# microcontroller.net
KiCad netlist of a schematic drawn in Altium Designer
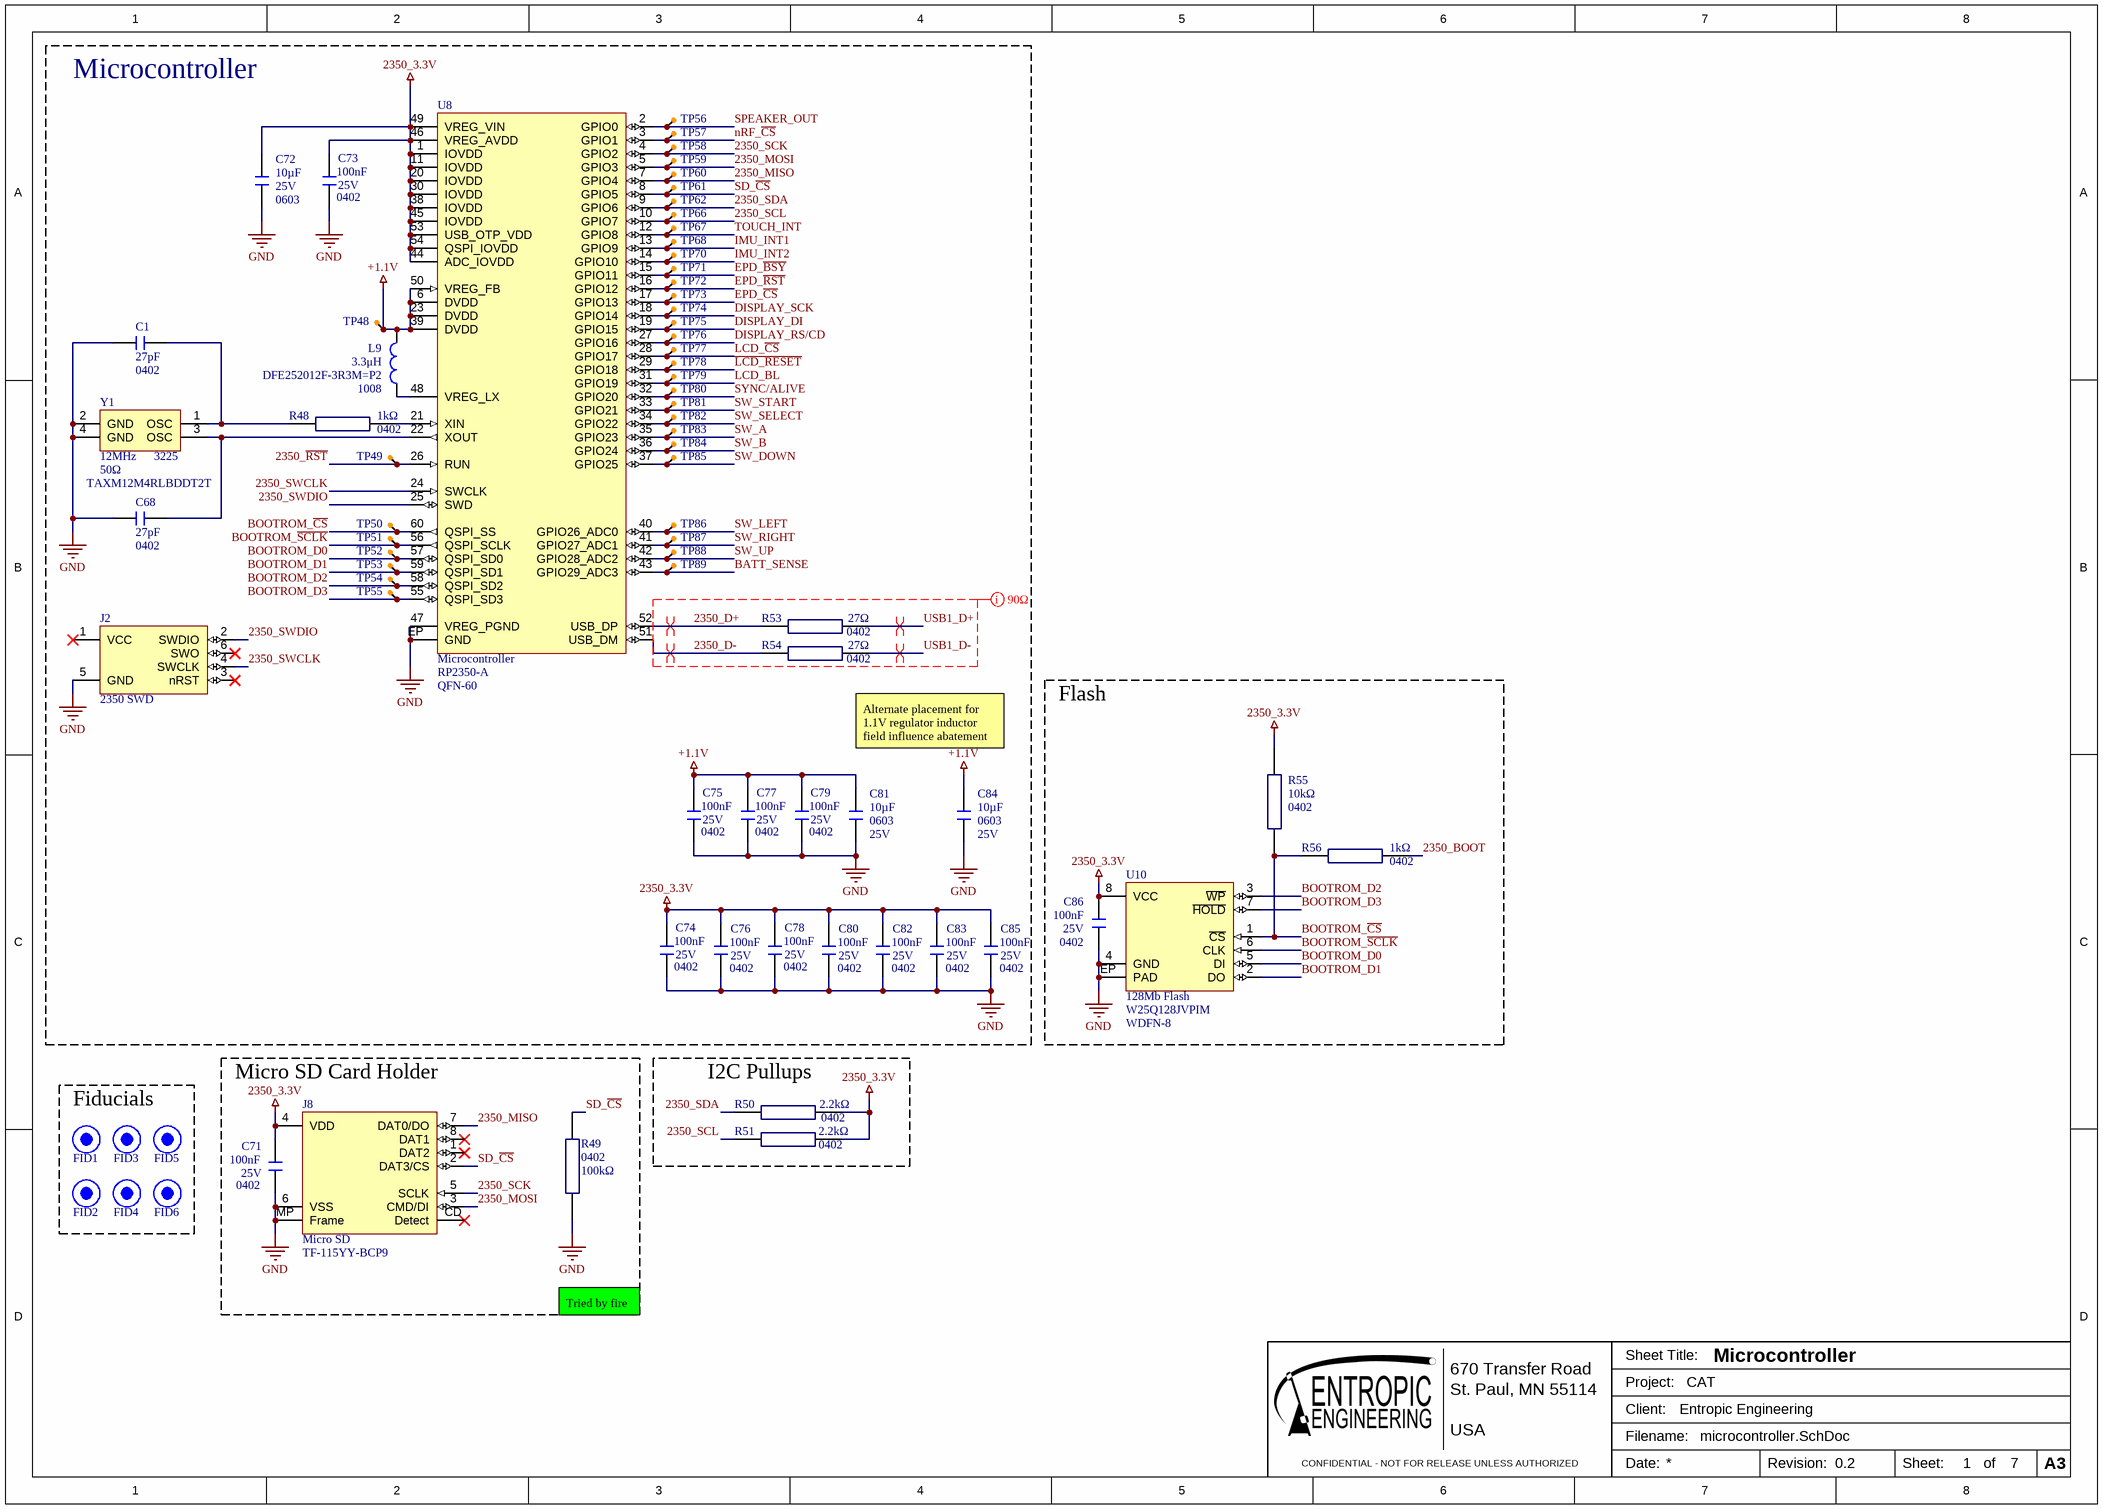
[diagram p0: microcontroller.SchDoc]

(export (version "E")
  (design (tool "Eeschema 10.0.6"))
  (components
    (comp (ref "C1")
      (value "27pF")
      (footprint "0402_capacitor")
      (description "27 pF, 25 V, X7R, 0402 Chip capacitor")
      (fields
        (field (name "MANUFACTURER") "Yageo")
        (field (name "MANUFACTURER PART NUMBER") "CC0402JRNPO9BN270")
        (field (name "CASE/PACKAGE") "0402")
      )
      (libsource (lib "cat") (part "CC0402JRNPO9BN270"))
    )
    (comp (ref "C68")
      (value "27pF")
      (footprint "0402_capacitor")
      (description "27 pF, 25 V, X7R, 0402 Chip capacitor")
      (fields
        (field (name "MANUFACTURER") "Yageo")
        (field (name "MANUFACTURER PART NUMBER") "CC0402JRNPO9BN270")
        (field (name "CASE/PACKAGE") "0402")
      )
      (libsource (lib "cat") (part "CC0402JRNPO9BN270"))
    )
    (comp (ref "C71")
      (value "GRM155R71E104KE14D")
      (footprint "0402_capacitor")
      (description "100 nF, 25 V, X7R, 0402 Chip capacitor")
      (fields
        (field (name "MANUFACTURER") "Murata")
        (field (name "TOLERANCE") "10%")
        (field (name "CASE CODE (IMPERIAL)") "0402")
        (field (name "VOLTAGE") "25V")
        (field (name "CAPACITANCE") "100nF")
      )
      (libsource (lib "cat") (part "GRM155R71E104KE14D"))
    )
    (comp (ref "C72")
      (value "10µF")
      (footprint "0603_capacitor")
      (description "10 µF, 25 V, X5R, 0603 Chip capacitor")
      (fields
        (field (name "MANUFACTURER") "Samsung")
        (field (name "TOLERANCE") "20%")
        (field (name "VOLTAGE RATING") "25V")
        (field (name "CASE/PACKAGE") "0603")
      )
      (libsource (lib "cat") (part "CL10A106MA8NRNC"))
    )
    (comp (ref "C73")
      (value "GRM155R71E104KE14D")
      (footprint "0402_capacitor")
      (description "100 nF, 25 V, X7R, 0402 Chip capacitor")
      (fields
        (field (name "MANUFACTURER") "Murata")
        (field (name "TOLERANCE") "10%")
        (field (name "CASE CODE (IMPERIAL)") "0402")
        (field (name "VOLTAGE") "25V")
        (field (name "CAPACITANCE") "100nF")
      )
      (libsource (lib "cat") (part "GRM155R71E104KE14D"))
    )
    (comp (ref "C74")
      (value "GRM155R71E104KE14D")
      (footprint "0402_capacitor")
      (description "100 nF, 25 V, X7R, 0402 Chip capacitor")
      (fields
        (field (name "MANUFACTURER") "Murata")
        (field (name "TOLERANCE") "10%")
        (field (name "CASE CODE (IMPERIAL)") "0402")
        (field (name "VOLTAGE") "25V")
        (field (name "CAPACITANCE") "100nF")
      )
      (libsource (lib "cat") (part "GRM155R71E104KE14D"))
    )
    (comp (ref "C75")
      (value "GRM155R71E104KE14D")
      (footprint "0402_capacitor")
      (description "100 nF, 25 V, X7R, 0402 Chip capacitor")
      (fields
        (field (name "MANUFACTURER") "Murata")
        (field (name "TOLERANCE") "10%")
        (field (name "CASE CODE (IMPERIAL)") "0402")
        (field (name "VOLTAGE") "25V")
        (field (name "CAPACITANCE") "100nF")
      )
      (libsource (lib "cat") (part "GRM155R71E104KE14D"))
    )
    (comp (ref "C76")
      (value "GRM155R71E104KE14D")
      (footprint "0402_capacitor")
      (description "100 nF, 25 V, X7R, 0402 Chip capacitor")
      (fields
        (field (name "MANUFACTURER") "Murata")
        (field (name "TOLERANCE") "10%")
        (field (name "CASE CODE (IMPERIAL)") "0402")
        (field (name "VOLTAGE") "25V")
        (field (name "CAPACITANCE") "100nF")
      )
      (libsource (lib "cat") (part "GRM155R71E104KE14D"))
    )
    (comp (ref "C77")
      (value "GRM155R71E104KE14D")
      (footprint "0402_capacitor")
      (description "100 nF, 25 V, X7R, 0402 Chip capacitor")
      (fields
        (field (name "MANUFACTURER") "Murata")
        (field (name "TOLERANCE") "10%")
        (field (name "CASE CODE (IMPERIAL)") "0402")
        (field (name "VOLTAGE") "25V")
        (field (name "CAPACITANCE") "100nF")
      )
      (libsource (lib "cat") (part "GRM155R71E104KE14D"))
    )
    (comp (ref "C78")
      (value "GRM155R71E104KE14D")
      (footprint "0402_capacitor")
      (description "100 nF, 25 V, X7R, 0402 Chip capacitor")
      (fields
        (field (name "MANUFACTURER") "Murata")
        (field (name "TOLERANCE") "10%")
        (field (name "CASE CODE (IMPERIAL)") "0402")
        (field (name "VOLTAGE") "25V")
        (field (name "CAPACITANCE") "100nF")
      )
      (libsource (lib "cat") (part "GRM155R71E104KE14D"))
    )
    (comp (ref "C79")
      (value "GRM155R71E104KE14D")
      (footprint "0402_capacitor")
      (description "100 nF, 25 V, X7R, 0402 Chip capacitor")
      (fields
        (field (name "MANUFACTURER") "Murata")
        (field (name "TOLERANCE") "10%")
        (field (name "CASE CODE (IMPERIAL)") "0402")
        (field (name "VOLTAGE") "25V")
        (field (name "CAPACITANCE") "100nF")
      )
      (libsource (lib "cat") (part "GRM155R71E104KE14D"))
    )
    (comp (ref "C80")
      (value "GRM155R71E104KE14D")
      (footprint "0402_capacitor")
      (description "100 nF, 25 V, X7R, 0402 Chip capacitor")
      (fields
        (field (name "MANUFACTURER") "Murata")
        (field (name "TOLERANCE") "10%")
        (field (name "CASE CODE (IMPERIAL)") "0402")
        (field (name "VOLTAGE") "25V")
        (field (name "CAPACITANCE") "100nF")
      )
      (libsource (lib "cat") (part "GRM155R71E104KE14D"))
    )
    (comp (ref "C81")
      (value "10µF")
      (footprint "0603_capacitor")
      (description "10 µF, 25 V, X5R, 0603 Chip capacitor")
      (fields
        (field (name "MANUFACTURER") "Samsung")
        (field (name "TOLERANCE") "20%")
        (field (name "VOLTAGE RATING") "25V")
        (field (name "CASE/PACKAGE") "0603")
      )
      (libsource (lib "cat") (part "CL10A106MA8NRNC"))
    )
    (comp (ref "C82")
      (value "GRM155R71E104KE14D")
      (footprint "0402_capacitor")
      (description "100 nF, 25 V, X7R, 0402 Chip capacitor")
      (fields
        (field (name "MANUFACTURER") "Murata")
        (field (name "TOLERANCE") "10%")
        (field (name "CASE CODE (IMPERIAL)") "0402")
        (field (name "VOLTAGE") "25V")
        (field (name "CAPACITANCE") "100nF")
      )
      (libsource (lib "cat") (part "GRM155R71E104KE14D"))
    )
    (comp (ref "C83")
      (value "GRM155R71E104KE14D")
      (footprint "0402_capacitor")
      (description "100 nF, 25 V, X7R, 0402 Chip capacitor")
      (fields
        (field (name "MANUFACTURER") "Murata")
        (field (name "TOLERANCE") "10%")
        (field (name "CASE CODE (IMPERIAL)") "0402")
        (field (name "VOLTAGE") "25V")
        (field (name "CAPACITANCE") "100nF")
      )
      (libsource (lib "cat") (part "GRM155R71E104KE14D"))
    )
    (comp (ref "C84")
      (value "10µF")
      (footprint "0603_capacitor")
      (description "10 µF, 25 V, X5R, 0603 Chip capacitor")
      (fields
        (field (name "MANUFACTURER") "Samsung")
        (field (name "TOLERANCE") "20%")
        (field (name "VOLTAGE RATING") "25V")
        (field (name "CASE/PACKAGE") "0603")
      )
      (libsource (lib "cat") (part "CL10A106MA8NRNC"))
    )
    (comp (ref "C85")
      (value "GRM155R71E104KE14D")
      (footprint "0402_capacitor")
      (description "100 nF, 25 V, X7R, 0402 Chip capacitor")
      (fields
        (field (name "MANUFACTURER") "Murata")
        (field (name "TOLERANCE") "10%")
        (field (name "CASE CODE (IMPERIAL)") "0402")
        (field (name "VOLTAGE") "25V")
        (field (name "CAPACITANCE") "100nF")
      )
      (libsource (lib "cat") (part "GRM155R71E104KE14D"))
    )
    (comp (ref "C86")
      (value "GRM155R71E104KE14D")
      (footprint "0402_capacitor")
      (description "100 nF, 25 V, X7R, 0402 Chip capacitor")
      (fields
        (field (name "MANUFACTURER") "Murata")
        (field (name "TOLERANCE") "10%")
        (field (name "CASE CODE (IMPERIAL)") "0402")
        (field (name "VOLTAGE") "25V")
        (field (name "CAPACITANCE") "100nF")
      )
      (libsource (lib "cat") (part "GRM155R71E104KE14D"))
    )
    (comp (ref "FID1")
      (value "fiducial")
      (footprint "fiducial-0.5")
      (description "0.5mm diameter round fiducial")
      (fields (field (name "HOUSE_PART_NUMBER") "Disc-0.5"))
      (libsource (lib "cat") (part "fiducial"))
    )
    (comp (ref "FID2")
      (value "fiducial")
      (footprint "fiducial-0.5")
      (description "0.5mm diameter round fiducial")
      (fields (field (name "HOUSE_PART_NUMBER") "Disc-0.5"))
      (libsource (lib "cat") (part "fiducial"))
    )
    (comp (ref "FID3")
      (value "fiducial")
      (footprint "fiducial-0.5")
      (description "0.5mm diameter round fiducial")
      (fields (field (name "HOUSE_PART_NUMBER") "Disc-0.5"))
      (libsource (lib "cat") (part "fiducial"))
    )
    (comp (ref "FID4")
      (value "fiducial")
      (footprint "fiducial-0.5")
      (description "0.5mm diameter round fiducial")
      (fields (field (name "HOUSE_PART_NUMBER") "Disc-0.5"))
      (libsource (lib "cat") (part "fiducial"))
    )
    (comp (ref "FID5")
      (value "fiducial")
      (footprint "fiducial-0.5")
      (description "0.5mm diameter round fiducial")
      (fields (field (name "HOUSE_PART_NUMBER") "Disc-0.5"))
      (libsource (lib "cat") (part "fiducial"))
    )
    (comp (ref "FID6")
      (value "fiducial")
      (footprint "fiducial-0.5")
      (description "0.5mm diameter round fiducial")
      (fields (field (name "HOUSE_PART_NUMBER") "Disc-0.5"))
      (libsource (lib "cat") (part "fiducial"))
    )
    (comp (ref "J2")
      (value "2350 SWD")
      (footprint "debug_header_dual")
      (description "Mates with TC-2030-CTX-NL")
      (fields (field (name "HOUSE_PART_NUMBER") "type-value-case-grade"))
      (libsource (lib "cat") (part "TAG_CONN_CTX"))
    )
    (comp (ref "J8")
      (value "Micro SD")
      (footprint "TF-115YY-BCP9")
      (description "Micro SD card holder")
      (fields
        (field (name "MANUFACTURER") "Xunpu")
        (field (name "MANUFACTURER PART NUMBER") "TF-115YY-BCP9")
        (field (name "HOUSE_PART_NUMBER") "TF-115YY-BCP9")
      )
      (libsource (lib "cat") (part "TF-115YY-BCP9"))
    )
    (comp (ref "L9")
      (value "3.3μH")
      (footprint "INDC2520X12N")
      (description "3.3 μH, 1.8 A, 1008 Inductor")
      (fields
        (field (name "MANUFACTURER") "Murata")
        (field (name "TOLERANCE") "20%")
        (field (name "CASE CODE (IMPERIAL)") "1008")
        (field (name "MANUFACTURER PART NUMBER") "DFE252012F-3R3M=P2")
      )
      (libsource (lib "cat") (part "DFE252012F-3R3M=P2"))
    )
    (comp (ref "R48")
      (value "1kΩ")
      (footprint "0402_resistor")
      (description "1 kΩ, 0402 Chip resistor")
      (fields
        (field (name "MANUFACTURER") "Yageo")
        (field (name "MANUFACTURER PART NUMBER") "RC0402JR-071KL")
        (field (name "CASE/PACKAGE") "0402")
      )
      (libsource (lib "cat") (part "RC0402JR-071KL"))
    )
    (comp (ref "R49")
      (value "100kΩ")
      (footprint "0402_resistor")
      (description "100 kΩ, 0402 Chip resistor")
      (fields
        (field (name "MANUFACTURER") "Yageo")
        (field (name "MANUFACTURER PART NUMBER") "RC0402FR-07100KL")
        (field (name "CASE/PACKAGE") "0402")
      )
      (libsource (lib "cat") (part "RC0402FR-07100KL"))
    )
    (comp (ref "R50")
      (value "2.2kΩ")
      (footprint "0402_resistor")
      (description "2.2 kΩ, 0402 Chip resistor")
      (fields
        (field (name "MANUFACTURER") "Yageo")
        (field (name "MANUFACTURER PART NUMBER") "RC0402FR-072K2L")
        (field (name "CASE/PACKAGE") "0402")
      )
      (libsource (lib "cat") (part "RC0402FR-072K2L"))
    )
    (comp (ref "R51")
      (value "2.2kΩ")
      (footprint "0402_resistor")
      (description "2.2 kΩ, 0402 Chip resistor")
      (fields
        (field (name "MANUFACTURER") "Yageo")
        (field (name "MANUFACTURER PART NUMBER") "RC0402FR-072K2L")
        (field (name "CASE/PACKAGE") "0402")
      )
      (libsource (lib "cat") (part "RC0402FR-072K2L"))
    )
    (comp (ref "R53")
      (value "RMCF0402FT27R0")
      (footprint "0402_resistor")
      (description "27 Ω, 0402 Chip resistor")
      (fields
        (field (name "MANUFACTURER") "Stackpole Electronics")
        (field (name "TOLERANCE") "1%")
        (field (name "RESISTANCE") "27Ω")
        (field (name "SIZE CODE") "0402")
      )
      (libsource (lib "cat") (part "RMCF0402FT27R0"))
    )
    (comp (ref "R54")
      (value "RMCF0402FT27R0")
      (footprint "0402_resistor")
      (description "27 Ω, 0402 Chip resistor")
      (fields
        (field (name "MANUFACTURER") "Stackpole Electronics")
        (field (name "TOLERANCE") "1%")
        (field (name "RESISTANCE") "27Ω")
        (field (name "SIZE CODE") "0402")
      )
      (libsource (lib "cat") (part "RMCF0402FT27R0"))
    )
    (comp (ref "R55")
      (value "RMCF0402FT10K0")
      (footprint "0402_resistor")
      (description "10 kΩ, 0402 Chip resistor")
      (fields
        (field (name "MANUFACTURER") "Stackpole Electronics")
        (field (name "TOLERANCE") "1%")
        (field (name "CASE CODE (IMPERIAL)") "0402")
        (field (name "RESISTANCE") "10kΩ")
      )
      (libsource (lib "cpc") (part "RMCF0402FT10K0"))
    )
    (comp (ref "R56")
      (value "1kΩ")
      (footprint "0402_resistor")
      (description "1 kΩ, 0402 Chip resistor")
      (fields
        (field (name "MANUFACTURER") "Yageo")
        (field (name "MANUFACTURER PART NUMBER") "RC0402JR-071KL")
        (field (name "CASE/PACKAGE") "0402")
      )
      (libsource (lib "cpc") (part "RC0402JR-071KL"))
    )
    (comp (ref "TP48")
      (value "+1.1V")
      (footprint "test_point-1")
      (description "Test point")
      (libsource (lib "cat") (part "test_point-1"))
    )
    (comp (ref "TP49")
      (value "test_point-1")
      (footprint "test_point-1")
      (description "Test point")
      (libsource (lib "cat") (part "test_point-1"))
    )
    (comp (ref "TP50")
      (value "test_point-1")
      (footprint "test_point-1")
      (description "Test point")
      (libsource (lib "cat") (part "test_point-1"))
    )
    (comp (ref "TP51")
      (value "test_point-1")
      (footprint "test_point-1")
      (description "Test point")
      (libsource (lib "cat") (part "test_point-1"))
    )
    (comp (ref "TP52")
      (value "test_point-1")
      (footprint "test_point-1")
      (description "Test point")
      (libsource (lib "cat") (part "test_point-1"))
    )
    (comp (ref "TP53")
      (value "test_point-1")
      (footprint "test_point-1")
      (description "Test point")
      (libsource (lib "cat") (part "test_point-1"))
    )
    (comp (ref "TP54")
      (value "test_point-1")
      (footprint "test_point-1")
      (description "Test point")
      (libsource (lib "cat") (part "test_point-1"))
    )
    (comp (ref "TP55")
      (value "test_point-1")
      (footprint "test_point-1")
      (description "Test point")
      (libsource (lib "cat") (part "test_point-1"))
    )
    (comp (ref "TP56")
      (value "test_point-1")
      (footprint "test_point-1")
      (description "Test point")
      (libsource (lib "cat") (part "test_point-1"))
    )
    (comp (ref "TP57")
      (value "test_point-1")
      (footprint "test_point-1")
      (description "Test point")
      (libsource (lib "cat") (part "test_point-1"))
    )
    (comp (ref "TP58")
      (value "test_point-1")
      (footprint "test_point-1")
      (description "Test point")
      (libsource (lib "cat") (part "test_point-1"))
    )
    (comp (ref "TP59")
      (value "test_point-1")
      (footprint "test_point-1")
      (description "Test point")
      (libsource (lib "cat") (part "test_point-1"))
    )
    (comp (ref "TP60")
      (value "test_point-1")
      (footprint "test_point-1")
      (description "Test point")
      (libsource (lib "cat") (part "test_point-1"))
    )
    (comp (ref "TP61")
      (value "test_point-1")
      (footprint "test_point-1")
      (description "Test point")
      (libsource (lib "cat") (part "test_point-1"))
    )
    (comp (ref "TP62")
      (value "test_point-1")
      (footprint "test_point-1")
      (description "Test point")
      (libsource (lib "cat") (part "test_point-1"))
    )
    (comp (ref "TP66")
      (value "test_point-1")
      (footprint "test_point-1")
      (description "Test point")
      (libsource (lib "cat") (part "test_point-1"))
    )
    (comp (ref "TP67")
      (value "test_point-1")
      (footprint "test_point-1")
      (description "Test point")
      (libsource (lib "cat") (part "test_point-1"))
    )
    (comp (ref "TP68")
      (value "test_point-1")
      (footprint "test_point-1")
      (description "Test point")
      (libsource (lib "cat") (part "test_point-1"))
    )
    (comp (ref "TP70")
      (value "test_point-1")
      (footprint "test_point-1")
      (description "Test point")
      (libsource (lib "cat") (part "test_point-1"))
    )
    (comp (ref "TP71")
      (value "test_point-1")
      (footprint "test_point-1")
      (description "Test point")
      (libsource (lib "cat") (part "test_point-1"))
    )
    (comp (ref "TP72")
      (value "test_point-1")
      (footprint "test_point-1")
      (description "Test point")
      (libsource (lib "cat") (part "test_point-1"))
    )
    (comp (ref "TP73")
      (value "test_point-1")
      (footprint "test_point-1")
      (description "Test point")
      (libsource (lib "cat") (part "test_point-1"))
    )
    (comp (ref "TP74")
      (value "test_point-1")
      (footprint "test_point-1")
      (description "Test point")
      (libsource (lib "cat") (part "test_point-1"))
    )
    (comp (ref "TP75")
      (value "test_point-1")
      (footprint "test_point-1")
      (description "Test point")
      (libsource (lib "cat") (part "test_point-1"))
    )
    (comp (ref "TP76")
      (value "test_point-1")
      (footprint "test_point-1")
      (description "Test point")
      (libsource (lib "cat") (part "test_point-1"))
    )
    (comp (ref "TP77")
      (value "test_point-1")
      (footprint "test_point-1")
      (description "Test point")
      (libsource (lib "cat") (part "test_point-1"))
    )
    (comp (ref "TP78")
      (value "test_point-1")
      (footprint "test_point-1")
      (description "Test point")
      (libsource (lib "cat") (part "test_point-1"))
    )
    (comp (ref "TP79")
      (value "test_point-1")
      (footprint "test_point-1")
      (description "Test point")
      (libsource (lib "cat") (part "test_point-1"))
    )
    (comp (ref "TP80")
      (value "test_point-1")
      (footprint "test_point-1")
      (description "Test point")
      (libsource (lib "cat") (part "test_point-1"))
    )
    (comp (ref "TP81")
      (value "test_point-1")
      (footprint "test_point-1")
      (description "Test point")
      (libsource (lib "cat") (part "test_point-1"))
    )
    (comp (ref "TP82")
      (value "test_point-1")
      (footprint "test_point-1")
      (description "Test point")
      (libsource (lib "cat") (part "test_point-1"))
    )
    (comp (ref "TP83")
      (value "test_point-1")
      (footprint "test_point-1")
      (description "Test point")
      (libsource (lib "cat") (part "test_point-1"))
    )
    (comp (ref "TP84")
      (value "test_point-1")
      (footprint "test_point-1")
      (description "Test point")
      (libsource (lib "cat") (part "test_point-1"))
    )
    (comp (ref "TP85")
      (value "test_point-1")
      (footprint "test_point-1")
      (description "Test point")
      (libsource (lib "cat") (part "test_point-1"))
    )
    (comp (ref "TP86")
      (value "test_point-1")
      (footprint "test_point-1")
      (description "Test point")
      (libsource (lib "cat") (part "test_point-1"))
    )
    (comp (ref "TP87")
      (value "test_point-1")
      (footprint "test_point-1")
      (description "Test point")
      (libsource (lib "cat") (part "test_point-1"))
    )
    (comp (ref "TP88")
      (value "test_point-1")
      (footprint "test_point-1")
      (description "Test point")
      (libsource (lib "cat") (part "test_point-1"))
    )
    (comp (ref "TP89")
      (value "test_point-1")
      (footprint "test_point-1")
      (description "Test point")
      (libsource (lib "cat") (part "test_point-1"))
    )
    (comp (ref "U8")
      (value "Microcontroller")
      (footprint "PQFN40P700X700X80_HS-61N")
      (description "Microcontroller, QFN-60")
      (fields
        (field (name "MANUFACTURER") "Raspberry Pi")
        (field (name "PACKAGE") "QFN-60")
        (field (name "MANUFACTURER PART NUMBER") "RP2350-A")
        (field (name "HOUSE_PART_NUMBER") "RP2350-A")
      )
      (libsource (lib "cat") (part "RP2350-A"))
    )
    (comp (ref "U10")
      (value "128Mb Flash")
      (footprint "WDFN-8")
      (description "128Mb SPI flash memory")
      (fields
        (field (name "MANUFACTURER") "Winbond")
        (field (name "CASE/PACKAGE") "WDFN-8")
        (field (name "MANUFACTURER PART NUMBER") "W25Q128JVPIM")
      )
      (libsource (lib "cat") (part "W25Q128JVPIM"))
    )
    (comp (ref "Y1")
      (value "12MHz")
      (footprint "3225_crystal")
      (description "12 MHz, 10 ppm, 20 pF, 3225 Crystal")
      (fields
        (field (name "MANUFACTURER PART NUMBER") "TAXM12M4RLBDDT2T")
        (field (name "CASE/PACKAGE") "3225")
        (field (name "ESR") "50Ω")
        (field (name "HOUSE_PART_NUMBER") "TAXM12M4RLBDDT2T")
      )
      (libsource (lib "cat") (part "TAXM12M4RLBDDT2T"))
    )
  )
  (nets
    (net (code "1") (name "+1.1V") (class "Default")
      (node (ref "C75") (pin "2") (pinfunction "2_2") (pintype "passive"))
      (node (ref "C77") (pin "2") (pinfunction "2_2") (pintype "passive"))
      (node (ref "C79") (pin "2") (pinfunction "2_2") (pintype "passive"))
      (node (ref "C81") (pin "2") (pinfunction "2_2") (pintype "passive"))
      (node (ref "C84") (pin "2") (pinfunction "2_2") (pintype "passive"))
      (node (ref "L9") (pin "2") (pinfunction "2_2") (pintype "passive"))
      (node (ref "TP48") (pin "1") (pinfunction "1_1") (pintype "passive"))
      (node (ref "U8") (pin "23") (pinfunction "DVDD_23") (pintype "power_in"))
      (node (ref "U8") (pin "39") (pinfunction "DVDD_39") (pintype "power_in"))
      (node (ref "U8") (pin "50") (pinfunction "VREG_FB_50") (pintype "input"))
      (node (ref "U8") (pin "6") (pinfunction "DVDD_6") (pintype "power_in"))
    )
    (net (code "2") (name "/2350_BOOT") (class "Default")
      (node (ref "R56") (pin "2") (pinfunction "2_2") (pintype "passive"))
    )
    (net (code "3") (name "/2350_D+") (class "Default")
      (node (ref "R53") (pin "1") (pinfunction "1_1") (pintype "passive"))
      (node (ref "U8") (pin "52") (pinfunction "USB_DP_52") (pintype "bidirectional"))
    )
    (net (code "4") (name "/2350_D-") (class "Default")
      (node (ref "R54") (pin "1") (pinfunction "1_1") (pintype "passive"))
      (node (ref "U8") (pin "51") (pinfunction "USB_DM_51") (pintype "bidirectional"))
    )
    (net (code "5") (name "/2350_MISO") (class "Default")
      (node (ref "J8") (pin "7") (pinfunction "DAT0/DO_7") (pintype "bidirectional"))
      (node (ref "TP60") (pin "1") (pinfunction "1_1") (pintype "passive"))
      (node (ref "U8") (pin "7") (pinfunction "GPIO4_7") (pintype "bidirectional"))
    )
    (net (code "6") (name "/2350_MOSI") (class "Default")
      (node (ref "J8") (pin "3") (pinfunction "CMD/DI_3") (pintype "bidirectional"))
      (node (ref "TP59") (pin "1") (pinfunction "1_1") (pintype "passive"))
      (node (ref "U8") (pin "5") (pinfunction "GPIO3_5") (pintype "bidirectional"))
    )
    (net (code "7") (name "/2350_SCK") (class "Default")
      (node (ref "J8") (pin "5") (pinfunction "SCLK_5") (pintype "input"))
      (node (ref "TP58") (pin "1") (pinfunction "1_1") (pintype "passive"))
      (node (ref "U8") (pin "4") (pinfunction "GPIO2_4") (pintype "bidirectional"))
    )
    (net (code "8") (name "/2350_SCL") (class "Default")
      (node (ref "R51") (pin "2") (pinfunction "2_2") (pintype "passive"))
      (node (ref "TP66") (pin "1") (pinfunction "1_1") (pintype "passive"))
      (node (ref "U8") (pin "10") (pinfunction "GPIO7_10") (pintype "bidirectional"))
    )
    (net (code "9") (name "/2350_SDA") (class "Default")
      (node (ref "R50") (pin "2") (pinfunction "2_2") (pintype "passive"))
      (node (ref "TP62") (pin "1") (pinfunction "1_1") (pintype "passive"))
      (node (ref "U8") (pin "9") (pinfunction "GPIO6_9") (pintype "bidirectional"))
    )
    (net (code "10") (name "/2350_SWCLK") (class "Default")
      (node (ref "J2") (pin "4") (pinfunction "SWCLK_4") (pintype "bidirectional"))
      (node (ref "U8") (pin "24") (pinfunction "SWCLK_24") (pintype "input"))
    )
    (net (code "11") (name "/2350_SWDIO") (class "Default")
      (node (ref "J2") (pin "2") (pinfunction "SWDIO_2") (pintype "bidirectional"))
      (node (ref "U8") (pin "25") (pinfunction "SWD_25") (pintype "bidirectional"))
    )
    (net (code "12") (name "/2350_~{RST}") (class "Default")
      (node (ref "TP49") (pin "1") (pinfunction "1_1") (pintype "passive"))
      (node (ref "U8") (pin "26") (pinfunction "RUN_26") (pintype "input"))
    )
    (net (code "13") (name "/BATT_SENSE") (class "Default")
      (node (ref "TP89") (pin "1") (pinfunction "1_1") (pintype "passive"))
      (node (ref "U8") (pin "43") (pinfunction "GPIO29_ADC3_43") (pintype "bidirectional"))
    )
    (net (code "14") (name "/BOOTROM_D0") (class "Default")
      (node (ref "TP52") (pin "1") (pinfunction "1_1") (pintype "passive"))
      (node (ref "U10") (pin "5") (pinfunction "DI_5") (pintype "bidirectional"))
      (node (ref "U8") (pin "57") (pinfunction "QSPI_SD0_57") (pintype "bidirectional"))
    )
    (net (code "15") (name "/BOOTROM_D1") (class "Default")
      (node (ref "TP53") (pin "1") (pinfunction "1_1") (pintype "passive"))
      (node (ref "U10") (pin "2") (pinfunction "DO_2") (pintype "bidirectional"))
      (node (ref "U8") (pin "59") (pinfunction "QSPI_SD1_59") (pintype "bidirectional"))
    )
    (net (code "16") (name "/BOOTROM_D2") (class "Default")
      (node (ref "TP54") (pin "1") (pinfunction "1_1") (pintype "passive"))
      (node (ref "U10") (pin "3") (pinfunction "~{WP}_3") (pintype "bidirectional"))
      (node (ref "U8") (pin "58") (pinfunction "QSPI_SD2_58") (pintype "bidirectional"))
    )
    (net (code "17") (name "/BOOTROM_D3") (class "Default")
      (node (ref "TP55") (pin "1") (pinfunction "1_1") (pintype "passive"))
      (node (ref "U10") (pin "7") (pinfunction "~{HOLD}_7") (pintype "bidirectional"))
      (node (ref "U8") (pin "55") (pinfunction "QSPI_SD3_55") (pintype "bidirectional"))
    )
    (net (code "18") (name "/BOOTROM_~{CS}") (class "Default")
      (node (ref "R55") (pin "2") (pinfunction "2_2") (pintype "passive"))
      (node (ref "R56") (pin "1") (pinfunction "1_1") (pintype "passive"))
      (node (ref "TP50") (pin "1") (pinfunction "1_1") (pintype "passive"))
      (node (ref "U10") (pin "1") (pinfunction "~{CS}_1") (pintype "input"))
      (node (ref "U8") (pin "60") (pinfunction "QSPI_SS_60") (pintype "output"))
    )
    (net (code "19") (name "/BOOTROM_~{SCLK}") (class "Default")
      (node (ref "TP51") (pin "1") (pinfunction "1_1") (pintype "passive"))
      (node (ref "U10") (pin "6") (pinfunction "CLK_6") (pintype "input"))
      (node (ref "U8") (pin "56") (pinfunction "QSPI_SCLK_56") (pintype "output"))
    )
    (net (code "20") (name "/DISPLAY_DI") (class "Default")
      (node (ref "TP75") (pin "1") (pinfunction "1_1") (pintype "passive"))
      (node (ref "U8") (pin "19") (pinfunction "GPIO15_19") (pintype "bidirectional"))
    )
    (net (code "21") (name "/DISPLAY_RS{slash}CD") (class "Default")
      (node (ref "TP76") (pin "1") (pinfunction "1_1") (pintype "passive"))
      (node (ref "U8") (pin "27") (pinfunction "GPIO16_27") (pintype "bidirectional"))
    )
    (net (code "22") (name "/DISPLAY_SCK") (class "Default")
      (node (ref "TP74") (pin "1") (pinfunction "1_1") (pintype "passive"))
      (node (ref "U8") (pin "18") (pinfunction "GPIO14_18") (pintype "bidirectional"))
    )
    (net (code "23") (name "/EPD_~{BSY}") (class "Default")
      (node (ref "TP71") (pin "1") (pinfunction "1_1") (pintype "passive"))
      (node (ref "U8") (pin "15") (pinfunction "GPIO11_15") (pintype "bidirectional"))
    )
    (net (code "24") (name "/EPD_~{CS}") (class "Default")
      (node (ref "TP73") (pin "1") (pinfunction "1_1") (pintype "passive"))
      (node (ref "U8") (pin "17") (pinfunction "GPIO13_17") (pintype "bidirectional"))
    )
    (net (code "25") (name "/EPD_~{RST}") (class "Default")
      (node (ref "TP72") (pin "1") (pinfunction "1_1") (pintype "passive"))
      (node (ref "U8") (pin "16") (pinfunction "GPIO12_16") (pintype "bidirectional"))
    )
    (net (code "26") (name "/IMU_INT1") (class "Default")
      (node (ref "TP68") (pin "1") (pinfunction "1_1") (pintype "passive"))
      (node (ref "U8") (pin "13") (pinfunction "GPIO9_13") (pintype "bidirectional"))
    )
    (net (code "27") (name "/IMU_INT2") (class "Default")
      (node (ref "TP70") (pin "1") (pinfunction "1_1") (pintype "passive"))
      (node (ref "U8") (pin "14") (pinfunction "GPIO10_14") (pintype "bidirectional"))
    )
    (net (code "28") (name "/LCD_BL") (class "Default")
      (node (ref "TP79") (pin "1") (pinfunction "1_1") (pintype "passive"))
      (node (ref "U8") (pin "31") (pinfunction "GPIO19_31") (pintype "bidirectional"))
    )
    (net (code "29") (name "/LCD_RESET") (class "Default")
      (node (ref "TP78") (pin "1") (pinfunction "1_1") (pintype "passive"))
      (node (ref "U8") (pin "29") (pinfunction "GPIO18_29") (pintype "bidirectional"))
    )
    (net (code "30") (name "/LCD_~{CS}") (class "Default")
      (node (ref "TP77") (pin "1") (pinfunction "1_1") (pintype "passive"))
      (node (ref "U8") (pin "28") (pinfunction "GPIO17_28") (pintype "bidirectional"))
    )
    (net (code "31") (name "/SD_~{CS}") (class "Default")
      (node (ref "J8") (pin "2") (pinfunction "DAT3/CS_2") (pintype "bidirectional"))
      (node (ref "R49") (pin "2") (pinfunction "2_2") (pintype "passive"))
      (node (ref "TP61") (pin "1") (pinfunction "1_1") (pintype "passive"))
      (node (ref "U8") (pin "8") (pinfunction "GPIO5_8") (pintype "bidirectional"))
    )
    (net (code "32") (name "/SPEAKER_OUT") (class "Default")
      (node (ref "TP56") (pin "1") (pinfunction "1_1") (pintype "passive"))
      (node (ref "U8") (pin "2") (pinfunction "GPIO0_2") (pintype "bidirectional"))
    )
    (net (code "33") (name "/SW_A") (class "Default")
      (node (ref "TP83") (pin "1") (pinfunction "1_1") (pintype "passive"))
      (node (ref "U8") (pin "35") (pinfunction "GPIO23_35") (pintype "bidirectional"))
    )
    (net (code "34") (name "/SW_B") (class "Default")
      (node (ref "TP84") (pin "1") (pinfunction "1_1") (pintype "passive"))
      (node (ref "U8") (pin "36") (pinfunction "GPIO24_36") (pintype "bidirectional"))
    )
    (net (code "35") (name "/SW_DOWN") (class "Default")
      (node (ref "TP85") (pin "1") (pinfunction "1_1") (pintype "passive"))
      (node (ref "U8") (pin "37") (pinfunction "GPIO25_37") (pintype "bidirectional"))
    )
    (net (code "36") (name "/SW_LEFT") (class "Default")
      (node (ref "TP86") (pin "1") (pinfunction "1_1") (pintype "passive"))
      (node (ref "U8") (pin "40") (pinfunction "GPIO26_ADC0_40") (pintype "bidirectional"))
    )
    (net (code "37") (name "/SW_RIGHT") (class "Default")
      (node (ref "TP87") (pin "1") (pinfunction "1_1") (pintype "passive"))
      (node (ref "U8") (pin "41") (pinfunction "GPIO27_ADC1_41") (pintype "bidirectional"))
    )
    (net (code "38") (name "/SW_SELECT") (class "Default")
      (node (ref "TP82") (pin "1") (pinfunction "1_1") (pintype "passive"))
      (node (ref "U8") (pin "34") (pinfunction "GPIO22_34") (pintype "bidirectional"))
    )
    (net (code "39") (name "/SW_START") (class "Default")
      (node (ref "TP81") (pin "1") (pinfunction "1_1") (pintype "passive"))
      (node (ref "U8") (pin "33") (pinfunction "GPIO21_33") (pintype "bidirectional"))
    )
    (net (code "40") (name "/SW_UP") (class "Default")
      (node (ref "TP88") (pin "1") (pinfunction "1_1") (pintype "passive"))
      (node (ref "U8") (pin "42") (pinfunction "GPIO28_ADC2_42") (pintype "bidirectional"))
    )
    (net (code "41") (name "/SYNC{slash}ALIVE") (class "Default")
      (node (ref "TP80") (pin "1") (pinfunction "1_1") (pintype "passive"))
      (node (ref "U8") (pin "32") (pinfunction "GPIO20_32") (pintype "bidirectional"))
    )
    (net (code "42") (name "/TOUCH_INT") (class "Default")
      (node (ref "TP67") (pin "1") (pinfunction "1_1") (pintype "passive"))
      (node (ref "U8") (pin "12") (pinfunction "GPIO8_12") (pintype "bidirectional"))
    )
    (net (code "43") (name "/USB1_D+") (class "Default")
      (node (ref "R53") (pin "2") (pinfunction "2_2") (pintype "passive"))
    )
    (net (code "44") (name "/USB1_D-") (class "Default")
      (node (ref "R54") (pin "2") (pinfunction "2_2") (pintype "passive"))
    )
    (net (code "45") (name "/nRF_~{CS}") (class "Default")
      (node (ref "TP57") (pin "1") (pinfunction "1_1") (pintype "passive"))
      (node (ref "U8") (pin "3") (pinfunction "GPIO1_3") (pintype "bidirectional"))
    )
    (net (code "46") (name "2350_3.3V") (class "Default")
      (node (ref "C71") (pin "2") (pinfunction "2_2") (pintype "passive"))
      (node (ref "C72") (pin "2") (pinfunction "2_2") (pintype "passive"))
      (node (ref "C73") (pin "2") (pinfunction "2_2") (pintype "passive"))
      (node (ref "C74") (pin "2") (pinfunction "2_2") (pintype "passive"))
      (node (ref "C76") (pin "2") (pinfunction "2_2") (pintype "passive"))
      (node (ref "C78") (pin "2") (pinfunction "2_2") (pintype "passive"))
      (node (ref "C80") (pin "2") (pinfunction "2_2") (pintype "passive"))
      (node (ref "C82") (pin "2") (pinfunction "2_2") (pintype "passive"))
      (node (ref "C83") (pin "2") (pinfunction "2_2") (pintype "passive"))
      (node (ref "C85") (pin "2") (pinfunction "2_2") (pintype "passive"))
      (node (ref "C86") (pin "2") (pinfunction "2_2") (pintype "passive"))
      (node (ref "J8") (pin "4") (pinfunction "VDD_4") (pintype "power_in"))
      (node (ref "R50") (pin "1") (pinfunction "1_1") (pintype "passive"))
      (node (ref "R51") (pin "1") (pinfunction "1_1") (pintype "passive"))
      (node (ref "R55") (pin "1") (pinfunction "1_1") (pintype "passive"))
      (node (ref "U10") (pin "8") (pinfunction "VCC_8") (pintype "power_in"))
      (node (ref "U8") (pin "1") (pinfunction "IOVDD_1") (pintype "power_in"))
      (node (ref "U8") (pin "11") (pinfunction "IOVDD_11") (pintype "power_in"))
      (node (ref "U8") (pin "20") (pinfunction "IOVDD_20") (pintype "power_in"))
      (node (ref "U8") (pin "30") (pinfunction "IOVDD_30") (pintype "power_in"))
      (node (ref "U8") (pin "38") (pinfunction "IOVDD_38") (pintype "power_in"))
      (node (ref "U8") (pin "44") (pinfunction "ADC_IOVDD_44") (pintype "power_in"))
      (node (ref "U8") (pin "45") (pinfunction "IOVDD_45") (pintype "power_in"))
      (node (ref "U8") (pin "46") (pinfunction "VREG_AVDD_46") (pintype "power_in"))
      (node (ref "U8") (pin "49") (pinfunction "VREG_VIN_49") (pintype "power_in"))
      (node (ref "U8") (pin "53") (pinfunction "USB_OTP_VDD_53") (pintype "power_in"))
      (node (ref "U8") (pin "54") (pinfunction "QSPI_IOVDD_54") (pintype "power_in"))
    )
    (net (code "47") (name "GND") (class "Default")
      (node (ref "C1") (pin "1") (pinfunction "1_1") (pintype "passive"))
      (node (ref "C68") (pin "1") (pinfunction "1_1") (pintype "passive"))
      (node (ref "C71") (pin "1") (pinfunction "1_1") (pintype "passive"))
      (node (ref "C72") (pin "1") (pinfunction "1_1") (pintype "passive"))
      (node (ref "C73") (pin "1") (pinfunction "1_1") (pintype "passive"))
      (node (ref "C74") (pin "1") (pinfunction "1_1") (pintype "passive"))
      (node (ref "C75") (pin "1") (pinfunction "1_1") (pintype "passive"))
      (node (ref "C76") (pin "1") (pinfunction "1_1") (pintype "passive"))
      (node (ref "C77") (pin "1") (pinfunction "1_1") (pintype "passive"))
      (node (ref "C78") (pin "1") (pinfunction "1_1") (pintype "passive"))
      (node (ref "C79") (pin "1") (pinfunction "1_1") (pintype "passive"))
      (node (ref "C80") (pin "1") (pinfunction "1_1") (pintype "passive"))
      (node (ref "C81") (pin "1") (pinfunction "1_1") (pintype "passive"))
      (node (ref "C82") (pin "1") (pinfunction "1_1") (pintype "passive"))
      (node (ref "C83") (pin "1") (pinfunction "1_1") (pintype "passive"))
      (node (ref "C84") (pin "1") (pinfunction "1_1") (pintype "passive"))
      (node (ref "C85") (pin "1") (pinfunction "1_1") (pintype "passive"))
      (node (ref "C86") (pin "1") (pinfunction "1_1") (pintype "passive"))
      (node (ref "J2") (pin "5") (pinfunction "GND_5") (pintype "power_in"))
      (node (ref "J8") (pin "6") (pinfunction "VSS_6") (pintype "power_in"))
      (node (ref "J8") (pin "MP") (pinfunction "Frame_MP") (pintype "power_in"))
      (node (ref "R49") (pin "1") (pinfunction "1_1") (pintype "passive"))
      (node (ref "U10") (pin "4") (pinfunction "GND_4") (pintype "power_in"))
      (node (ref "U10") (pin "EP") (pinfunction "PAD_EP") (pintype "power_in"))
      (node (ref "U8") (pin "47") (pinfunction "VREG_PGND_47") (pintype "power_in"))
      (node (ref "U8") (pin "EP") (pinfunction "GND_EP") (pintype "power_in"))
      (node (ref "Y1") (pin "2") (pinfunction "GND_2") (pintype "power_in"))
      (node (ref "Y1") (pin "4") (pinfunction "GND_4") (pintype "power_in"))
    )
    (net (code "48") (name "Net-(C1-Pad2)") (class "Default")
      (node (ref "C1") (pin "2") (pinfunction "2_2") (pintype "passive"))
      (node (ref "R48") (pin "1") (pinfunction "1_1") (pintype "passive"))
      (node (ref "Y1") (pin "1") (pinfunction "OSC_1") (pintype "passive"))
    )
    (net (code "49") (name "Net-(U8-VREG_LX)") (class "Default")
      (node (ref "L9") (pin "1") (pinfunction "1_1") (pintype "passive"))
      (node (ref "U8") (pin "48") (pinfunction "VREG_LX_48") (pintype "power_in"))
    )
    (net (code "50") (name "Net-(U8-XIN)") (class "Default")
      (node (ref "R48") (pin "2") (pinfunction "2_2") (pintype "passive"))
      (node (ref "U8") (pin "21") (pinfunction "XIN_21") (pintype "input"))
    )
    (net (code "51") (name "Net-(U8-XOUT)") (class "Default")
      (node (ref "C68") (pin "2") (pinfunction "2_2") (pintype "passive"))
      (node (ref "U8") (pin "22") (pinfunction "XOUT_22") (pintype "output"))
      (node (ref "Y1") (pin "3") (pinfunction "OSC_3") (pintype "passive"))
    )
    (net (code "52") (name "unconnected-(J2-SWO-Pad6)") (class "Default")
      (node (ref "J2") (pin "6") (pinfunction "SWO_6") (pintype "bidirectional+no_connect"))
    )
    (net (code "53") (name "unconnected-(J2-VCC-Pad1)") (class "Default")
      (node (ref "J2") (pin "1") (pinfunction "VCC_1") (pintype "power_in+no_connect"))
    )
    (net (code "54") (name "unconnected-(J2-nRST-Pad3)") (class "Default")
      (node (ref "J2") (pin "3") (pinfunction "nRST_3") (pintype "bidirectional+no_connect"))
    )
    (net (code "55") (name "unconnected-(J8-DAT1-Pad8)") (class "Default")
      (node (ref "J8") (pin "8") (pinfunction "DAT1_8") (pintype "bidirectional+no_connect"))
    )
    (net (code "56") (name "unconnected-(J8-DAT2-Pad1)") (class "Default")
      (node (ref "J8") (pin "1") (pinfunction "DAT2_1") (pintype "bidirectional+no_connect"))
    )
    (net (code "57") (name "unconnected-(J8-Detect-PadCD)") (class "Default")
      (node (ref "J8") (pin "CD") (pinfunction "Detect_CD") (pintype "passive+no_connect"))
    )
  )
)
